# Micro_Controller.net
KiCad netlist of a schematic drawn in Altium Designer
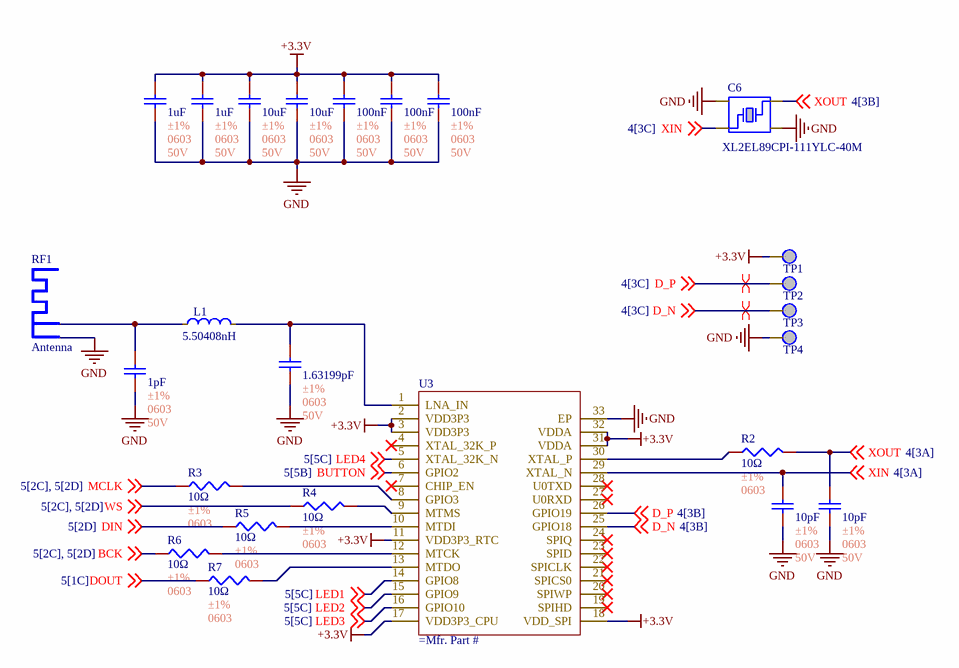
[diagram p0: Micro Controller.SchDoc]

(export (version "E")
  (design (tool "Eeschema 10.0.6"))
  (components
    (comp (ref "C6")
      (value "XL2EL89CPI-111YLC-40M")
      (footprint "XL2EL89CPI-111YLC-40M")
      (description "Crystal Oscillator 15pF SMD3225-4P Crystals RoHS")
      (fields (field (name "MANUFACTURER") "YXC Crystal Oscillators") (field (name "LCSC PART #") "C5444549"))
      (libsource (lib "Oscillator") (part "XL2EL89CPI-111YLC-40M"))
    )
    (comp (ref "C7")
      (value "1uF")
      (footprint "C0603")
      (description "50V 10pF NP0 ±1% 0402 Multilayer Ceramic Capacitors MLCC - SMD/SMT ROHS")
      (fields
        (field (name "MANUFACTURER") "YAGEO")
        (field (name "MFR. PART #") "CC0402FRNPO9BN100")
        (field (name "TOLERANCE") "±1%")
        (field (name "PACKAGE") "0603")
        (field (name "VOLTAGE RATING") "50V")
      )
      (libsource (lib "Capital") (part "C0603_1uF_±1%"))
    )
    (comp (ref "C8")
      (value "1uF")
      (footprint "C0603")
      (description "50V 10pF NP0 ±1% 0402 Multilayer Ceramic Capacitors MLCC - SMD/SMT ROHS")
      (fields
        (field (name "MANUFACTURER") "YAGEO")
        (field (name "MFR. PART #") "CC0402FRNPO9BN100")
        (field (name "TOLERANCE") "±1%")
        (field (name "PACKAGE") "0603")
        (field (name "VOLTAGE RATING") "50V")
      )
      (libsource (lib "Capital") (part "C0603_1uF_±1%"))
    )
    (comp (ref "C9")
      (value "10uF")
      (footprint "C0603")
      (description "50V 10pF NP0 ±1% 0402 Multilayer Ceramic Capacitors MLCC - SMD/SMT ROHS")
      (fields
        (field (name "MANUFACTURER") "YAGEO")
        (field (name "MFR. PART #") "CC0402FRNPO9BN100")
        (field (name "TOLERANCE") "±1%")
        (field (name "PACKAGE") "0603")
        (field (name "VOLTAGE RATING") "50V")
      )
      (libsource (lib "Capital") (part "C0603_10uF_±1%"))
    )
    (comp (ref "C10")
      (value "10uF")
      (footprint "C0603")
      (description "50V 10pF NP0 ±1% 0402 Multilayer Ceramic Capacitors MLCC - SMD/SMT ROHS")
      (fields
        (field (name "MANUFACTURER") "YAGEO")
        (field (name "MFR. PART #") "CC0402FRNPO9BN100")
        (field (name "TOLERANCE") "±1%")
        (field (name "PACKAGE") "0603")
        (field (name "VOLTAGE RATING") "50V")
      )
      (libsource (lib "Capital") (part "C0603_10uF_±1%"))
    )
    (comp (ref "C11")
      (value "100nF")
      (footprint "C0603")
      (description "50V 10pF NP0 ±1% 0402 Multilayer Ceramic Capacitors MLCC - SMD/SMT ROHS")
      (fields
        (field (name "MANUFACTURER") "YAGEO")
        (field (name "MFR. PART #") "CC0402FRNPO9BN100")
        (field (name "TOLERANCE") "±1%")
        (field (name "PACKAGE") "0603")
        (field (name "VOLTAGE RATING") "50V")
      )
      (libsource (lib "Capital") (part "C0603_100nF_±1%"))
    )
    (comp (ref "C12")
      (value "100nF")
      (footprint "C0603")
      (description "50V 10pF NP0 ±1% 0402 Multilayer Ceramic Capacitors MLCC - SMD/SMT ROHS")
      (fields
        (field (name "MANUFACTURER") "YAGEO")
        (field (name "MFR. PART #") "CC0402FRNPO9BN100")
        (field (name "TOLERANCE") "±1%")
        (field (name "PACKAGE") "0603")
        (field (name "VOLTAGE RATING") "50V")
      )
      (libsource (lib "Capital") (part "C0603_100nF_±1%"))
    )
    (comp (ref "C13")
      (value "100nF")
      (footprint "C0603")
      (description "50V 10pF NP0 ±1% 0402 Multilayer Ceramic Capacitors MLCC - SMD/SMT ROHS")
      (fields
        (field (name "MANUFACTURER") "YAGEO")
        (field (name "MFR. PART #") "CC0402FRNPO9BN100")
        (field (name "TOLERANCE") "±1%")
        (field (name "PACKAGE") "0603")
        (field (name "VOLTAGE RATING") "50V")
      )
      (libsource (lib "Capital") (part "C0603_100nF_±1%"))
    )
    (comp (ref "C14")
      (value "1pF")
      (footprint "C0603")
      (description "50V 10pF NP0 ±1% 0402 Multilayer Ceramic Capacitors MLCC - SMD/SMT ROHS")
      (fields
        (field (name "MANUFACTURER") "YAGEO")
        (field (name "MFR. PART #") "CC0402FRNPO9BN100")
        (field (name "TOLERANCE") "±1%")
        (field (name "PACKAGE") "0603")
        (field (name "VOLTAGE RATING") "50V")
      )
      (libsource (lib "Capital") (part "C0603_10pF_±1%"))
    )
    (comp (ref "C15")
      (value "1.63199pF")
      (footprint "C0603")
      (description "50V 10pF NP0 ±1% 0402 Multilayer Ceramic Capacitors MLCC - SMD/SMT ROHS")
      (fields
        (field (name "MANUFACTURER") "YAGEO")
        (field (name "MFR. PART #") "CC0402FRNPO9BN100")
        (field (name "TOLERANCE") "±1%")
        (field (name "PACKAGE") "0603")
        (field (name "VOLTAGE RATING") "50V")
      )
      (libsource (lib "Capital") (part "C0603_10pF_±1%"))
    )
    (comp (ref "C16")
      (value "10pF")
      (footprint "C0603")
      (description "50V 10pF NP0 ±1% 0402 Multilayer Ceramic Capacitors MLCC - SMD/SMT ROHS")
      (fields
        (field (name "MANUFACTURER") "YAGEO")
        (field (name "MFR. PART #") "CC0402FRNPO9BN100")
        (field (name "TOLERANCE") "±1%")
        (field (name "PACKAGE") "0603")
        (field (name "VOLTAGE RATING") "50V")
      )
      (libsource (lib "Capital") (part "C0603_10pF_±1%"))
    )
    (comp (ref "C17")
      (value "10pF")
      (footprint "C0603")
      (description "50V 10pF NP0 ±1% 0402 Multilayer Ceramic Capacitors MLCC - SMD/SMT ROHS")
      (fields
        (field (name "MANUFACTURER") "YAGEO")
        (field (name "MFR. PART #") "CC0402FRNPO9BN100")
        (field (name "TOLERANCE") "±1%")
        (field (name "PACKAGE") "0603")
        (field (name "VOLTAGE RATING") "50V")
      )
      (libsource (lib "Capital") (part "C0603_10pF_±1%"))
    )
    (comp (ref "L1")
      (value "5.50408nH")
      (footprint "0603CT-3N0XGRW")
      (description "1.6A 3nH 39mΩ Wire-wound chip inductor ±2% 0603 Fixed Inductors RoHS")
      (fields (field (name "MANUFACTURER") "Coilcraft") (field (name "MFR. PART #") "0603CT-3N0XGRW"))
      (libsource (lib "Inductor") (part "L_3nH_3.6A_0603"))
    )
    (comp (ref "R2")
      (value "10Ω")
      (footprint "R0603")
      (description "62.5mW Thick Film Resistor 50V ±1% ±200ppm/℃ 10Ω 0402 Chip Resistor - Surface Mount ROHS")
      (fields
        (field (name "MANUFACTURER") "YAGEO")
        (field (name "MFR. PART #") "RC0402FR-0710RL")
        (field (name "TOLERANCE") "±1%")
        (field (name "PACKAGE") "0603")
      )
      (libsource (lib "Resistor") (part "R0603_10Ω_±1%"))
    )
    (comp (ref "R3")
      (value "10Ω")
      (footprint "R0603")
      (description "62.5mW Thick Film Resistor 50V ±1% ±200ppm/℃ 10Ω 0402 Chip Resistor - Surface Mount ROHS")
      (fields
        (field (name "MANUFACTURER") "YAGEO")
        (field (name "MFR. PART #") "RC0402FR-0710RL")
        (field (name "TOLERANCE") "±1%")
        (field (name "PACKAGE") "0603")
      )
      (libsource (lib "Resistor") (part "R0603_10Ω_±1%"))
    )
    (comp (ref "R4")
      (value "10Ω")
      (footprint "R0603")
      (description "62.5mW Thick Film Resistor 50V ±1% ±200ppm/℃ 10Ω 0402 Chip Resistor - Surface Mount ROHS")
      (fields
        (field (name "MANUFACTURER") "YAGEO")
        (field (name "MFR. PART #") "RC0402FR-0710RL")
        (field (name "TOLERANCE") "±1%")
        (field (name "PACKAGE") "0603")
      )
      (libsource (lib "Resistor") (part "R0603_10Ω_±1%"))
    )
    (comp (ref "R5")
      (value "10Ω")
      (footprint "R0603")
      (description "62.5mW Thick Film Resistor 50V ±1% ±200ppm/℃ 10Ω 0402 Chip Resistor - Surface Mount ROHS")
      (fields
        (field (name "MANUFACTURER") "YAGEO")
        (field (name "MFR. PART #") "RC0402FR-0710RL")
        (field (name "TOLERANCE") "±1%")
        (field (name "PACKAGE") "0603")
      )
      (libsource (lib "Resistor") (part "R0603_10Ω_±1%"))
    )
    (comp (ref "R6")
      (value "10Ω")
      (footprint "R0603")
      (description "62.5mW Thick Film Resistor 50V ±1% ±200ppm/℃ 10Ω 0402 Chip Resistor - Surface Mount ROHS")
      (fields
        (field (name "MANUFACTURER") "YAGEO")
        (field (name "MFR. PART #") "RC0402FR-0710RL")
        (field (name "TOLERANCE") "±1%")
        (field (name "PACKAGE") "0603")
      )
      (libsource (lib "Resistor") (part "R0603_10Ω_±1%"))
    )
    (comp (ref "R7")
      (value "10Ω")
      (footprint "R0603")
      (description "62.5mW Thick Film Resistor 50V ±1% ±200ppm/℃ 10Ω 0402 Chip Resistor - Surface Mount ROHS")
      (fields
        (field (name "MANUFACTURER") "YAGEO")
        (field (name "MFR. PART #") "RC0402FR-0710RL")
        (field (name "TOLERANCE") "±1%")
        (field (name "PACKAGE") "0603")
      )
      (libsource (lib "Resistor") (part "R0603_10Ω_±1%"))
    )
    (comp (ref "RF1")
      (value "Antenna")
      (footprint "2.4GHZ-50OHMS_v1.1")
      (libsource (lib "Antenna") (part "Antenna"))
    )
    (comp (ref "TP1") (value "TP") (footprint "TP") (libsource (lib "Other") (part "TP")))
    (comp (ref "TP2") (value "TP") (footprint "TP") (libsource (lib "Other") (part "TP")))
    (comp (ref "TP3") (value "TP") (footprint "TP") (libsource (lib "Other") (part "TP")))
    (comp (ref "TP4") (value "TP") (footprint "TP") (libsource (lib "Other") (part "TP")))
    (comp (ref "U3")
      (value "~")
      (footprint "ESP32-C3")
      (description "Others 160MHz QFN-32-EP(5x5) RF Transceiver Modules and Modems RoHS")
      (fields (field (name "MANUFACTURER") "ESPRESSIF") (field (name "LCSC PART #") "C2838500"))
      (libsource (lib "MCU") (part "ESP32-C3"))
    )
  )
  (nets
    (net (code "1") (name "+3.3V") (class "Default")
      (node (ref "C10") (pin "1") (pinfunction "1_1") (pintype "passive"))
      (node (ref "C11") (pin "1") (pinfunction "1_1") (pintype "passive"))
      (node (ref "C12") (pin "1") (pinfunction "1_1") (pintype "passive"))
      (node (ref "C13") (pin "1") (pinfunction "1_1") (pintype "passive"))
      (node (ref "C7") (pin "1") (pinfunction "1_1") (pintype "passive"))
      (node (ref "C8") (pin "1") (pinfunction "1_1") (pintype "passive"))
      (node (ref "C9") (pin "1") (pinfunction "1_1") (pintype "passive"))
      (node (ref "TP1") (pin "1") (pinfunction "1_1") (pintype "passive"))
      (node (ref "U3") (pin "11") (pinfunction "VDD3P3_RTC_11") (pintype "passive"))
      (node (ref "U3") (pin "17") (pinfunction "VDD3P3_CPU_17") (pintype "passive"))
      (node (ref "U3") (pin "18") (pinfunction "VDD_SPI_18") (pintype "passive"))
      (node (ref "U3") (pin "2") (pinfunction "VDD3P3_2") (pintype "passive"))
      (node (ref "U3") (pin "3") (pinfunction "VDD3P3_3") (pintype "passive"))
      (node (ref "U3") (pin "31") (pinfunction "VDDA_31") (pintype "passive"))
      (node (ref "U3") (pin "32") (pinfunction "VDDA_32") (pintype "passive"))
    )
    (net (code "2") (name "BCK") (class "Default")
      (node (ref "R6") (pin "1") (pinfunction "1_1") (pintype "passive"))
    )
    (net (code "3") (name "BUTTON") (class "Default")
      (node (ref "U3") (pin "6") (pinfunction "GPIO2_6") (pintype "passive"))
    )
    (net (code "4") (name "DIN") (class "Default")
      (node (ref "R5") (pin "1") (pinfunction "1_1") (pintype "passive"))
    )
    (net (code "5") (name "DOUT") (class "Default")
      (node (ref "R7") (pin "1") (pinfunction "1_1") (pintype "passive"))
    )
    (net (code "6") (name "D_N") (class "Default")
      (node (ref "TP3") (pin "1") (pinfunction "1_1") (pintype "passive"))
      (node (ref "U3") (pin "25") (pinfunction "GPIO18_25") (pintype "passive"))
    )
    (net (code "7") (name "D_P") (class "Default")
      (node (ref "TP2") (pin "1") (pinfunction "1_1") (pintype "passive"))
      (node (ref "U3") (pin "26") (pinfunction "GPIO19_26") (pintype "passive"))
    )
    (net (code "8") (name "GND") (class "Default")
      (node (ref "C10") (pin "2") (pinfunction "2_2") (pintype "passive"))
      (node (ref "C11") (pin "2") (pinfunction "2_2") (pintype "passive"))
      (node (ref "C12") (pin "2") (pinfunction "2_2") (pintype "passive"))
      (node (ref "C13") (pin "2") (pinfunction "2_2") (pintype "passive"))
      (node (ref "C14") (pin "2") (pinfunction "2_2") (pintype "passive"))
      (node (ref "C15") (pin "2") (pinfunction "2_2") (pintype "passive"))
      (node (ref "C16") (pin "2") (pinfunction "2_2") (pintype "passive"))
      (node (ref "C17") (pin "2") (pinfunction "2_2") (pintype "passive"))
      (node (ref "C6") (pin "2") (pinfunction "2_2") (pintype "passive"))
      (node (ref "C6") (pin "4") (pinfunction "4_4") (pintype "passive"))
      (node (ref "C7") (pin "2") (pinfunction "2_2") (pintype "passive"))
      (node (ref "C8") (pin "2") (pinfunction "2_2") (pintype "passive"))
      (node (ref "C9") (pin "2") (pinfunction "2_2") (pintype "passive"))
      (node (ref "RF1") (pin "2") (pinfunction "2_2") (pintype "passive"))
      (node (ref "TP4") (pin "1") (pinfunction "1_1") (pintype "passive"))
      (node (ref "U3") (pin "33") (pinfunction "EP_33") (pintype "passive"))
    )
    (net (code "9") (name "LED1") (class "Default")
      (node (ref "U3") (pin "14") (pinfunction "GPIO8_14") (pintype "passive"))
    )
    (net (code "10") (name "LED2") (class "Default")
      (node (ref "U3") (pin "15") (pinfunction "GPIO9_15") (pintype "passive"))
    )
    (net (code "11") (name "LED3") (class "Default")
      (node (ref "U3") (pin "16") (pinfunction "GPIO10_16") (pintype "passive"))
    )
    (net (code "12") (name "LED4") (class "Default")
      (node (ref "U3") (pin "5") (pinfunction "XTAL_32K_N_5") (pintype "passive"))
    )
    (net (code "13") (name "MCLK") (class "Default")
      (node (ref "R3") (pin "1") (pinfunction "1_1") (pintype "passive"))
    )
    (net (code "14") (name "Net-(C14-Pad1)") (class "Default")
      (node (ref "C14") (pin "1") (pinfunction "1_1") (pintype "passive"))
      (node (ref "L1") (pin "1") (pinfunction "1_1") (pintype "passive"))
      (node (ref "RF1") (pin "1") (pinfunction "1_1") (pintype "passive"))
    )
    (net (code "15") (name "Net-(U3-GPIO3)") (class "Default")
      (node (ref "R3") (pin "2") (pinfunction "2_2") (pintype "passive"))
      (node (ref "U3") (pin "8") (pinfunction "GPIO3_8") (pintype "passive"))
    )
    (net (code "16") (name "Net-(U3-LNA_IN)") (class "Default")
      (node (ref "C15") (pin "1") (pinfunction "1_1") (pintype "passive"))
      (node (ref "L1") (pin "2") (pinfunction "2_2") (pintype "passive"))
      (node (ref "U3") (pin "1") (pinfunction "LNA_IN_1") (pintype "passive"))
    )
    (net (code "17") (name "Net-(U3-MTCK)") (class "Default")
      (node (ref "R6") (pin "2") (pinfunction "2_2") (pintype "passive"))
      (node (ref "U3") (pin "12") (pinfunction "MTCK_12") (pintype "passive"))
    )
    (net (code "18") (name "Net-(U3-MTDI)") (class "Default")
      (node (ref "R5") (pin "2") (pinfunction "2_2") (pintype "passive"))
      (node (ref "U3") (pin "10") (pinfunction "MTDI_10") (pintype "passive"))
    )
    (net (code "19") (name "Net-(U3-MTDO)") (class "Default")
      (node (ref "R7") (pin "2") (pinfunction "2_2") (pintype "passive"))
      (node (ref "U3") (pin "13") (pinfunction "MTDO_13") (pintype "passive"))
    )
    (net (code "20") (name "Net-(U3-MTMS)") (class "Default")
      (node (ref "R4") (pin "2") (pinfunction "2_2") (pintype "passive"))
      (node (ref "U3") (pin "9") (pinfunction "MTMS_9") (pintype "passive"))
    )
    (net (code "21") (name "Net-(U3-XTAL_P)") (class "Default")
      (node (ref "R2") (pin "1") (pinfunction "1_1") (pintype "passive"))
      (node (ref "U3") (pin "30") (pinfunction "XTAL_P_30") (pintype "passive"))
    )
    (net (code "22") (name "WS") (class "Default")
      (node (ref "R4") (pin "1") (pinfunction "1_1") (pintype "passive"))
    )
    (net (code "23") (name "XIN") (class "Default")
      (node (ref "C16") (pin "1") (pinfunction "1_1") (pintype "passive"))
      (node (ref "C6") (pin "1") (pinfunction "1_1") (pintype "passive"))
      (node (ref "U3") (pin "29") (pinfunction "XTAL_N_29") (pintype "passive"))
    )
    (net (code "24") (name "XOUT") (class "Default")
      (node (ref "C17") (pin "1") (pinfunction "1_1") (pintype "passive"))
      (node (ref "C6") (pin "3") (pinfunction "3_3") (pintype "passive"))
      (node (ref "R2") (pin "2") (pinfunction "2_2") (pintype "passive"))
    )
    (net (code "25") (name "unconnected-(U3-CHIP_EN-Pad7)") (class "Default")
      (node (ref "U3") (pin "7") (pinfunction "CHIP_EN_7") (pintype "passive+no_connect"))
    )
    (net (code "26") (name "unconnected-(U3-SPICLK-Pad22)") (class "Default")
      (node (ref "U3") (pin "22") (pinfunction "SPICLK_22") (pintype "passive+no_connect"))
    )
    (net (code "27") (name "unconnected-(U3-SPICS0-Pad21)") (class "Default")
      (node (ref "U3") (pin "21") (pinfunction "SPICS0_21") (pintype "passive+no_connect"))
    )
    (net (code "28") (name "unconnected-(U3-SPID-Pad23)") (class "Default")
      (node (ref "U3") (pin "23") (pinfunction "SPID_23") (pintype "passive+no_connect"))
    )
    (net (code "29") (name "unconnected-(U3-SPIHD-Pad19)") (class "Default")
      (node (ref "U3") (pin "19") (pinfunction "SPIHD_19") (pintype "passive+no_connect"))
    )
    (net (code "30") (name "unconnected-(U3-SPIQ-Pad24)") (class "Default")
      (node (ref "U3") (pin "24") (pinfunction "SPIQ_24") (pintype "passive+no_connect"))
    )
    (net (code "31") (name "unconnected-(U3-SPIWP-Pad20)") (class "Default")
      (node (ref "U3") (pin "20") (pinfunction "SPIWP_20") (pintype "passive+no_connect"))
    )
    (net (code "32") (name "unconnected-(U3-U0RXD-Pad27)") (class "Default")
      (node (ref "U3") (pin "27") (pinfunction "U0RXD_27") (pintype "passive+no_connect"))
    )
    (net (code "33") (name "unconnected-(U3-U0TXD-Pad28)") (class "Default")
      (node (ref "U3") (pin "28") (pinfunction "U0TXD_28") (pintype "passive+no_connect"))
    )
    (net (code "34") (name "unconnected-(U3-XTAL_32K_P-Pad4)") (class "Default")
      (node (ref "U3") (pin "4") (pinfunction "XTAL_32K_P_4") (pintype "passive+no_connect"))
    )
  )
)
